# pi_gpio_snd.net
KiCad netlist of a schematic drawn in EAGLE
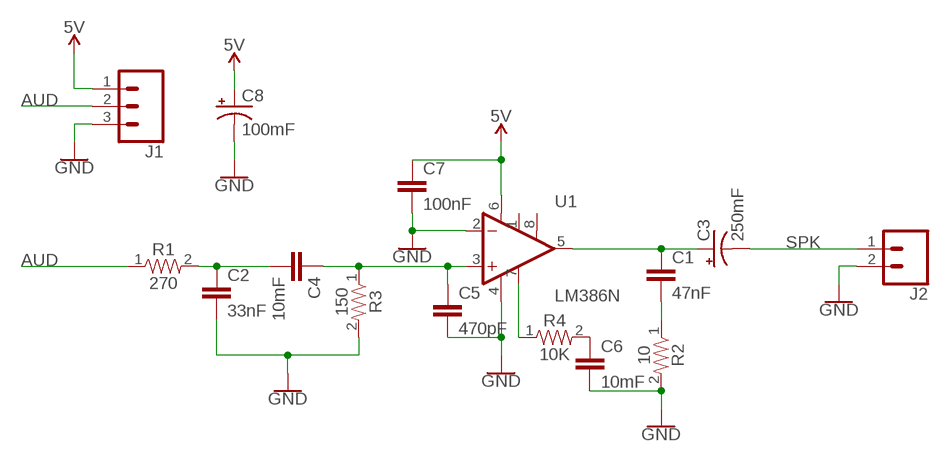
[diagram p0: schematic, sheet 1]

(export (version "E")
  (design (tool "Eeschema 10.0.6"))
  (components
    (comp (ref "C1")
      (value "47nF")
      (footprint "eagle-import:1206")
      (libsource (lib "eagle-import") (part "CAP-1206"))
    )
    (comp (ref "C2")
      (value "33nF")
      (footprint "eagle-import:1206")
      (libsource (lib "eagle-import") (part "CAP-1206"))
    )
    (comp (ref "C3")
      (value "250mF")
      (footprint "eagle-import:CPOL-RADIAL-5MM-10MM")
      (libsource (lib "eagle-import") (part "1000UF-RADIAL-5MM-25V-20%"))
    )
    (comp (ref "C4")
      (value "10mF")
      (footprint "eagle-import:0805")
      (libsource (lib "eagle-import") (part "CAP-805"))
    )
    (comp (ref "C5")
      (value "470pF")
      (footprint "eagle-import:1206")
      (libsource (lib "eagle-import") (part "CAP-1206"))
    )
    (comp (ref "C6")
      (value "10mF")
      (footprint "eagle-import:0805")
      (libsource (lib "eagle-import") (part "CAP-805"))
    )
    (comp (ref "C7")
      (value "100nF")
      (footprint "eagle-import:0805")
      (libsource (lib "eagle-import") (part "CAP-805"))
    )
    (comp (ref "C8")
      (value "100mF")
      (footprint "eagle-import:CPOL-RADIAL-5MM-10MM")
      (libsource (lib "eagle-import") (part "1000UF-RADIAL-5MM-25V-20%"))
    )
    (comp (ref "J1")
      (value "CONN_03")
      (footprint "eagle-import:1X03")
      (libsource (lib "eagle-import") (part "CONN_03"))
    )
    (comp (ref "J2")
      (value "CONN_02")
      (footprint "eagle-import:1X02")
      (libsource (lib "eagle-import") (part "CONN_02"))
    )
    (comp (ref "R1")
      (value "270")
      (footprint "eagle-import:1206")
      (libsource (lib "eagle-import") (part "RESISTOR-1206"))
    )
    (comp (ref "R2")
      (value "10")
      (footprint "eagle-import:1206")
      (libsource (lib "eagle-import") (part "RESISTOR-1206"))
    )
    (comp (ref "R3")
      (value "150")
      (footprint "eagle-import:1206")
      (libsource (lib "eagle-import") (part "RESISTOR-1206"))
    )
    (comp (ref "R4")
      (value "10K")
      (footprint "eagle-import:1206")
      (libsource (lib "eagle-import") (part "RESISTOR-1206"))
    )
    (comp (ref "U1")
      (value "LM386N")
      (footprint "eagle-import:DIP08")
      (libsource (lib "eagle-import") (part "LM386"))
    )
  )
  (nets
    (net (code "1") (name "/AUD") (class "Default")
      (node (ref "J1") (pin "2") (pinfunction "2_2") (pintype "passive"))
      (node (ref "R1") (pin "1") (pinfunction "1_1") (pintype "passive"))
    )
    (net (code "2") (name "/SPK") (class "Default")
      (node (ref "C3") (pin "-") (pinfunction "-_-") (pintype "passive"))
      (node (ref "J2") (pin "1") (pinfunction "1_1") (pintype "passive"))
    )
    (net (code "3") (name "5V") (class "Default")
      (node (ref "C7") (pin "1") (pinfunction "1_1") (pintype "passive"))
      (node (ref "C8") (pin "+") (pinfunction "+_+") (pintype "passive"))
      (node (ref "J1") (pin "1") (pinfunction "1_1") (pintype "passive"))
      (node (ref "U1") (pin "6") (pinfunction "V+_6") (pintype "power_in"))
    )
    (net (code "4") (name "GND") (class "Default")
      (node (ref "C2") (pin "2") (pinfunction "2_2") (pintype "passive"))
      (node (ref "C5") (pin "2") (pinfunction "2_2") (pintype "passive"))
      (node (ref "C6") (pin "2") (pinfunction "2_2") (pintype "passive"))
      (node (ref "C7") (pin "2") (pinfunction "2_2") (pintype "passive"))
      (node (ref "C8") (pin "-") (pinfunction "-_-") (pintype "passive"))
      (node (ref "J1") (pin "3") (pinfunction "3_3") (pintype "passive"))
      (node (ref "J2") (pin "2") (pinfunction "2_2") (pintype "passive"))
      (node (ref "R2") (pin "2") (pinfunction "2_2") (pintype "passive"))
      (node (ref "R3") (pin "2") (pinfunction "2_2") (pintype "passive"))
      (node (ref "U1") (pin "2") (pinfunction "-IN_2") (pintype "input"))
      (node (ref "U1") (pin "4") (pinfunction "V-_4") (pintype "power_in"))
    )
    (net (code "5") (name "Net-(C1-Pad2)") (class "Default")
      (node (ref "C1") (pin "2") (pinfunction "2_2") (pintype "passive"))
      (node (ref "R2") (pin "1") (pinfunction "1_1") (pintype "passive"))
    )
    (net (code "6") (name "Net-(C2-Pad1)") (class "Default")
      (node (ref "C2") (pin "1") (pinfunction "1_1") (pintype "passive"))
      (node (ref "C4") (pin "2") (pinfunction "2_2") (pintype "passive"))
      (node (ref "R1") (pin "2") (pinfunction "2_2") (pintype "passive"))
    )
    (net (code "7") (name "Net-(C6-Pad1)") (class "Default")
      (node (ref "C6") (pin "1") (pinfunction "1_1") (pintype "passive"))
      (node (ref "R4") (pin "2") (pinfunction "2_2") (pintype "passive"))
    )
    (net (code "8") (name "Net-(U1-+IN)") (class "Default")
      (node (ref "C4") (pin "1") (pinfunction "1_1") (pintype "passive"))
      (node (ref "C5") (pin "1") (pinfunction "1_1") (pintype "passive"))
      (node (ref "R3") (pin "1") (pinfunction "1_1") (pintype "passive"))
      (node (ref "U1") (pin "3") (pinfunction "+IN_3") (pintype "input"))
    )
    (net (code "9") (name "Net-(U1-BP)") (class "Default")
      (node (ref "R4") (pin "1") (pinfunction "1_1") (pintype "passive"))
      (node (ref "U1") (pin "7") (pinfunction "BP_7") (pintype "bidirectional"))
    )
    (net (code "10") (name "Net-(U1-OUT)") (class "Default")
      (node (ref "C1") (pin "1") (pinfunction "1_1") (pintype "passive"))
      (node (ref "C3") (pin "+") (pinfunction "+_+") (pintype "passive"))
      (node (ref "U1") (pin "5") (pinfunction "OUT_5") (pintype "output"))
    )
    (net (code "11") (name "unconnected-(U1-GAIN-Pad1)") (class "Default")
      (node (ref "U1") (pin "1") (pinfunction "GAIN_1") (pintype "bidirectional"))
    )
    (net (code "12") (name "unconnected-(U1-GAIN-Pad8)") (class "Default")
      (node (ref "U1") (pin "8") (pinfunction "GAIN_8") (pintype "bidirectional"))
    )
  )
)
